# questao4.net
KiCad netlist of a schematic drawn in EAGLE
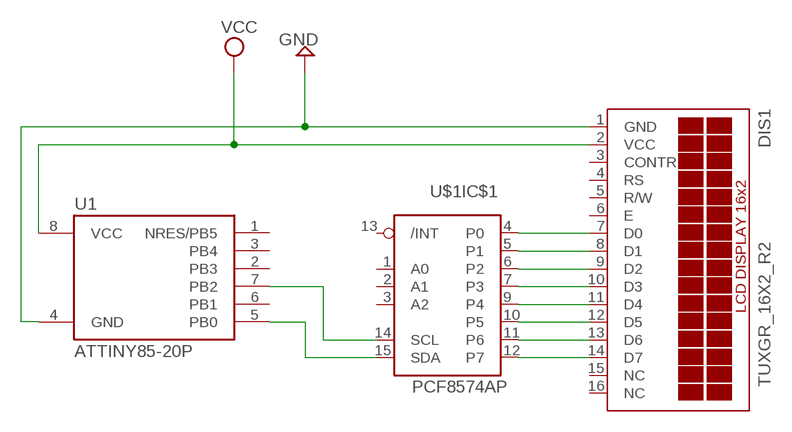
[diagram p0: schematic, sheet 1]

(export (version "E")
  (design (tool "Eeschema 10.0.6"))
  (components
    (comp (ref "DIS1")
      (value "TUXGR_16X2_R2")
      (footprint "eagle-import:TUXGR_16X2_R2")
      (libsource (lib "eagle-import") (part "TUXGR_16X2_R2"))
    )
    (comp (ref "U$1")
      (value "PCF8574AP")
      (footprint "eagle-import:DIL16")
      (libsource (lib "eagle-import") (part "PCF8574AP"))
    )
    (comp (ref "U1")
      (value "ATTINY85-20P")
      (footprint "eagle-import:PDIP08_300MIL")
      (libsource (lib "eagle-import") (part "ATTINY85P-20"))
    )
  )
  (nets
    (net (code "1") (name "GND") (class "Default")
      (node (ref "DIS1") (pin "1") (pinfunction "GND_1") (pintype "power_in"))
      (node (ref "U1") (pin "4") (pinfunction "GND_4") (pintype "power_in"))
    )
    (net (code "2") (name "Net-(DIS1-D0)") (class "Default")
      (node (ref "DIS1") (pin "7") (pinfunction "D0_7") (pintype "input"))
      (node (ref "U$1") (pin "4") (pinfunction "P0_4") (pintype "bidirectional"))
    )
    (net (code "3") (name "Net-(DIS1-D1)") (class "Default")
      (node (ref "DIS1") (pin "8") (pinfunction "D1_8") (pintype "input"))
      (node (ref "U$1") (pin "5") (pinfunction "P1_5") (pintype "bidirectional"))
    )
    (net (code "4") (name "Net-(DIS1-D2)") (class "Default")
      (node (ref "DIS1") (pin "9") (pinfunction "D2_9") (pintype "input"))
      (node (ref "U$1") (pin "6") (pinfunction "P2_6") (pintype "bidirectional"))
    )
    (net (code "5") (name "Net-(DIS1-D3)") (class "Default")
      (node (ref "DIS1") (pin "10") (pinfunction "D3_10") (pintype "input"))
      (node (ref "U$1") (pin "7") (pinfunction "P3_7") (pintype "bidirectional"))
    )
    (net (code "6") (name "Net-(DIS1-D4)") (class "Default")
      (node (ref "DIS1") (pin "11") (pinfunction "D4_11") (pintype "input"))
      (node (ref "U$1") (pin "9") (pinfunction "P4_9") (pintype "bidirectional"))
    )
    (net (code "7") (name "Net-(DIS1-D5)") (class "Default")
      (node (ref "DIS1") (pin "12") (pinfunction "D5_12") (pintype "input"))
      (node (ref "U$1") (pin "10") (pinfunction "P5_10") (pintype "bidirectional"))
    )
    (net (code "8") (name "Net-(DIS1-D6)") (class "Default")
      (node (ref "DIS1") (pin "13") (pinfunction "D6_13") (pintype "input"))
      (node (ref "U$1") (pin "11") (pinfunction "P6_11") (pintype "bidirectional"))
    )
    (net (code "9") (name "Net-(DIS1-D7)") (class "Default")
      (node (ref "DIS1") (pin "14") (pinfunction "D7_14") (pintype "input"))
      (node (ref "U$1") (pin "12") (pinfunction "P7_12") (pintype "bidirectional"))
    )
    (net (code "10") (name "Net-(U$1A-SCL)") (class "Default")
      (node (ref "U$1") (pin "14") (pinfunction "SCL_14") (pintype "input"))
      (node (ref "U1") (pin "7") (pinfunction "PB2_7") (pintype "bidirectional"))
    )
    (net (code "11") (name "Net-(U$1A-SDA)") (class "Default")
      (node (ref "U$1") (pin "15") (pinfunction "SDA_15") (pintype "bidirectional"))
      (node (ref "U1") (pin "5") (pinfunction "PB0_5") (pintype "bidirectional"))
    )
    (net (code "12") (name "VCC") (class "Default")
      (node (ref "DIS1") (pin "2") (pinfunction "VCC_2") (pintype "power_in"))
      (node (ref "U1") (pin "8") (pinfunction "VCC_8") (pintype "power_in"))
    )
    (net (code "13") (name "unconnected-(DIS1-CONTR-Pad3)") (class "Default")
      (node (ref "DIS1") (pin "3") (pinfunction "CONTR_3") (pintype "input"))
    )
    (net (code "14") (name "unconnected-(DIS1-E-Pad6)") (class "Default")
      (node (ref "DIS1") (pin "6") (pinfunction "E_6") (pintype "input"))
    )
    (net (code "15") (name "unconnected-(DIS1-NC-Pad15)") (class "Default")
      (node (ref "DIS1") (pin "15") (pinfunction "NC_15") (pintype "no_connect"))
    )
    (net (code "16") (name "unconnected-(DIS1-NC-Pad16)") (class "Default")
      (node (ref "DIS1") (pin "16") (pinfunction "NC_16") (pintype "no_connect"))
    )
    (net (code "17") (name "unconnected-(DIS1-RS-Pad4)") (class "Default")
      (node (ref "DIS1") (pin "4") (pinfunction "RS_4") (pintype "input"))
    )
    (net (code "18") (name "unconnected-(DIS1-R{slash}W-Pad5)") (class "Default")
      (node (ref "DIS1") (pin "5") (pinfunction "R/W_5") (pintype "input"))
    )
    (net (code "19") (name "unconnected-(U$1A-A0-Pad1)") (class "Default")
      (node (ref "U$1") (pin "1") (pinfunction "A0_1") (pintype "input"))
    )
    (net (code "20") (name "unconnected-(U$1A-A1-Pad2)") (class "Default")
      (node (ref "U$1") (pin "2") (pinfunction "A1_2") (pintype "input"))
    )
    (net (code "21") (name "unconnected-(U$1A-A2-Pad3)") (class "Default")
      (node (ref "U$1") (pin "3") (pinfunction "A2_3") (pintype "input"))
    )
    (net (code "22") (name "unconnected-(U$1A-{slash}INT-Pad13)") (class "Default")
      (node (ref "U$1") (pin "13") (pinfunction "/INT_13") (pintype "output"))
    )
    (net (code "23") (name "unconnected-(U1-NRES{slash}PB5-Pad1)") (class "Default")
      (node (ref "U1") (pin "1") (pinfunction "NRES/PB5_1") (pintype "bidirectional"))
    )
    (net (code "24") (name "unconnected-(U1-PB1-Pad6)") (class "Default")
      (node (ref "U1") (pin "6") (pinfunction "PB1_6") (pintype "bidirectional"))
    )
    (net (code "25") (name "unconnected-(U1-PB3-Pad2)") (class "Default")
      (node (ref "U1") (pin "2") (pinfunction "PB3_2") (pintype "bidirectional"))
    )
    (net (code "26") (name "unconnected-(U1-PB4-Pad3)") (class "Default")
      (node (ref "U1") (pin "3") (pinfunction "PB4_3") (pintype "bidirectional"))
    )
  )
)
